# w65c265sxb_ym2149_rev1.net
KiCad netlist of a schematic drawn in EAGLE
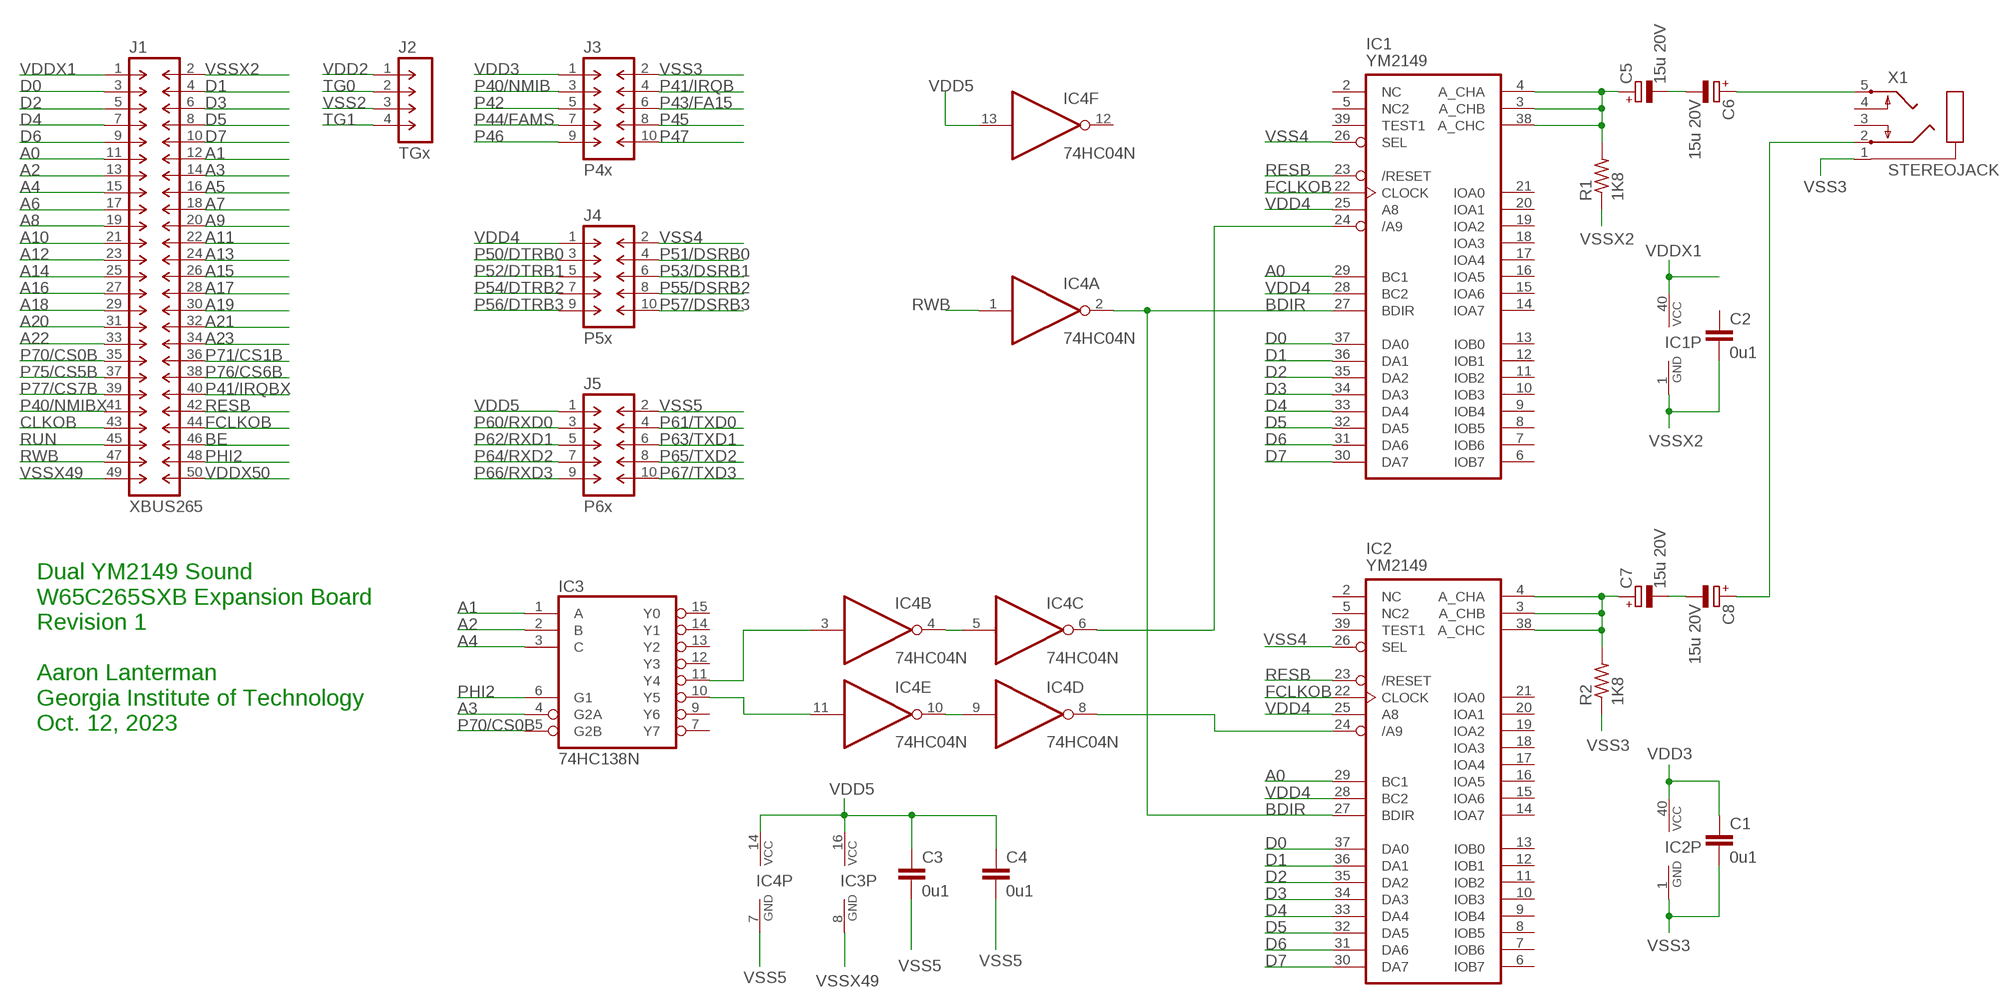
[diagram p0: schematic, sheet 1]

(export (version "E")
  (design (tool "Eeschema 10.0.6"))
  (components
    (comp (ref "C1")
      (value "0u1")
      (footprint "eagle-import:C050-025X075-AARON")
      (libsource (lib "eagle-import") (part "C-EU050-025X075-AARON"))
    )
    (comp (ref "C2")
      (value "0u1")
      (footprint "eagle-import:C050-025X075-AARON")
      (libsource (lib "eagle-import") (part "C-EU050-025X075-AARON"))
    )
    (comp (ref "C3")
      (value "0u1")
      (footprint "eagle-import:C050-025X075-AARON")
      (libsource (lib "eagle-import") (part "C-EU050-025X075-AARON"))
    )
    (comp (ref "C4")
      (value "0u1")
      (footprint "eagle-import:C050-025X075-AARON")
      (libsource (lib "eagle-import") (part "C-EU050-025X075-AARON"))
    )
    (comp (ref "C5")
      (value "15u 20V")
      (footprint "eagle-import:E2,5-7")
      (libsource (lib "eagle-import") (part "CPOL-EUE2.5-7"))
    )
    (comp (ref "C6")
      (value "15u 20V")
      (footprint "eagle-import:E2,5-7")
      (libsource (lib "eagle-import") (part "CPOL-EUE2.5-7"))
    )
    (comp (ref "C7")
      (value "15u 20V")
      (footprint "eagle-import:E2,5-7")
      (libsource (lib "eagle-import") (part "CPOL-EUE2.5-7"))
    )
    (comp (ref "C8")
      (value "15u 20V")
      (footprint "eagle-import:E2,5-7")
      (libsource (lib "eagle-import") (part "CPOL-EUE2.5-7"))
    )
    (comp (ref "IC1")
      (value "YM2149")
      (footprint "eagle-import:DIL40")
      (libsource (lib "eagle-import") (part "YM2149"))
    )
    (comp (ref "IC2")
      (value "YM2149")
      (footprint "eagle-import:DIL40")
      (libsource (lib "eagle-import") (part "YM2149"))
    )
    (comp (ref "IC3")
      (value "74HC138N")
      (footprint "eagle-import:DIL16")
      (libsource (lib "eagle-import") (part "74138NHC"))
    )
    (comp (ref "IC4")
      (value "74HC04N")
      (footprint "eagle-import:DIL14")
      (libsource (lib "eagle-import") (part "7404NHC"))
    )
    (comp (ref "J1")
      (value "XBUS265")
      (footprint "eagle-import:DIL-100-2X25")
      (libsource (lib "eagle-import") (part "M-2X25-DIL-100"))
    )
    (comp (ref "J2")
      (value "TGx")
      (footprint "eagle-import:SIP-100-04-40")
      (libsource (lib "eagle-import") (part "M-1X04-SIP-100-40"))
    )
    (comp (ref "J3")
      (value "P4x")
      (footprint "eagle-import:DIL-100-2X05")
      (libsource (lib "eagle-import") (part "M-2X05-DIL-100"))
    )
    (comp (ref "J4")
      (value "P5x")
      (footprint "eagle-import:DIL-100-2X05")
      (libsource (lib "eagle-import") (part "M-2X05-DIL-100"))
    )
    (comp (ref "J5")
      (value "P6x")
      (footprint "eagle-import:DIL-100-2X05")
      (libsource (lib "eagle-import") (part "M-2X05-DIL-100"))
    )
    (comp (ref "R1")
      (value "1K8")
      (footprint "eagle-import:0207_10")
      (libsource (lib "eagle-import") (part "R-US_0207/10"))
    )
    (comp (ref "R2")
      (value "1K8")
      (footprint "eagle-import:0207_10")
      (libsource (lib "eagle-import") (part "R-US_0207/10"))
    )
    (comp (ref "X1")
      (value "STEREOJACK")
      (footprint "eagle-import:STX3100")
      (libsource (lib "eagle-import") (part "STEREOJACK"))
    )
  )
  (nets
    (net (code "1") (name "/A0") (class "Default")
      (node (ref "IC1") (pin "29") (pinfunction "BC1_29") (pintype "input"))
      (node (ref "IC2") (pin "29") (pinfunction "BC1_29") (pintype "input"))
      (node (ref "J1") (pin "11") (pinfunction "11_11") (pintype "passive"))
    )
    (net (code "2") (name "/A1") (class "Default")
      (node (ref "IC3") (pin "1") (pinfunction "A_1") (pintype "input"))
      (node (ref "J1") (pin "12") (pinfunction "12_12") (pintype "passive"))
    )
    (net (code "3") (name "/A2") (class "Default")
      (node (ref "IC3") (pin "2") (pinfunction "B_2") (pintype "input"))
      (node (ref "J1") (pin "13") (pinfunction "13_13") (pintype "passive"))
    )
    (net (code "4") (name "/A3") (class "Default")
      (node (ref "IC3") (pin "4") (pinfunction "G2A_4") (pintype "input"))
      (node (ref "J1") (pin "14") (pinfunction "14_14") (pintype "passive"))
    )
    (net (code "5") (name "/A4") (class "Default")
      (node (ref "IC3") (pin "3") (pinfunction "C_3") (pintype "input"))
      (node (ref "J1") (pin "15") (pinfunction "15_15") (pintype "passive"))
    )
    (net (code "6") (name "/A5") (class "Default")
      (node (ref "J1") (pin "16") (pinfunction "16_16") (pintype "passive"))
    )
    (net (code "7") (name "/A6") (class "Default")
      (node (ref "J1") (pin "17") (pinfunction "17_17") (pintype "passive"))
    )
    (net (code "8") (name "/A7") (class "Default")
      (node (ref "J1") (pin "18") (pinfunction "18_18") (pintype "passive"))
    )
    (net (code "9") (name "/A8") (class "Default")
      (node (ref "J1") (pin "19") (pinfunction "19_19") (pintype "passive"))
    )
    (net (code "10") (name "/A9") (class "Default")
      (node (ref "J1") (pin "20") (pinfunction "20_20") (pintype "passive"))
    )
    (net (code "11") (name "/A10") (class "Default")
      (node (ref "J1") (pin "21") (pinfunction "21_21") (pintype "passive"))
    )
    (net (code "12") (name "/A11") (class "Default")
      (node (ref "J1") (pin "22") (pinfunction "22_22") (pintype "passive"))
    )
    (net (code "13") (name "/A12") (class "Default")
      (node (ref "J1") (pin "23") (pinfunction "23_23") (pintype "passive"))
    )
    (net (code "14") (name "/A13") (class "Default")
      (node (ref "J1") (pin "24") (pinfunction "24_24") (pintype "passive"))
    )
    (net (code "15") (name "/A14") (class "Default")
      (node (ref "J1") (pin "25") (pinfunction "25_25") (pintype "passive"))
    )
    (net (code "16") (name "/A15") (class "Default")
      (node (ref "J1") (pin "26") (pinfunction "26_26") (pintype "passive"))
    )
    (net (code "17") (name "/A16") (class "Default")
      (node (ref "J1") (pin "27") (pinfunction "27_27") (pintype "passive"))
    )
    (net (code "18") (name "/A17") (class "Default")
      (node (ref "J1") (pin "28") (pinfunction "28_28") (pintype "passive"))
    )
    (net (code "19") (name "/A18") (class "Default")
      (node (ref "J1") (pin "29") (pinfunction "29_29") (pintype "passive"))
    )
    (net (code "20") (name "/A19") (class "Default")
      (node (ref "J1") (pin "30") (pinfunction "30_30") (pintype "passive"))
    )
    (net (code "21") (name "/A20") (class "Default")
      (node (ref "J1") (pin "31") (pinfunction "31_31") (pintype "passive"))
    )
    (net (code "22") (name "/A21") (class "Default")
      (node (ref "J1") (pin "32") (pinfunction "32_32") (pintype "passive"))
    )
    (net (code "23") (name "/A22") (class "Default")
      (node (ref "J1") (pin "33") (pinfunction "33_33") (pintype "passive"))
    )
    (net (code "24") (name "/A23") (class "Default")
      (node (ref "J1") (pin "34") (pinfunction "34_34") (pintype "passive"))
    )
    (net (code "25") (name "/BDIR") (class "Default")
      (node (ref "IC1") (pin "27") (pinfunction "BDIR_27") (pintype "input"))
      (node (ref "IC2") (pin "27") (pinfunction "BDIR_27") (pintype "input"))
      (node (ref "IC4") (pin "2") (pinfunction "O_2") (pintype "output"))
    )
    (net (code "26") (name "/BE") (class "Default")
      (node (ref "J1") (pin "46") (pinfunction "46_46") (pintype "passive"))
    )
    (net (code "27") (name "/CLKOB") (class "Default")
      (node (ref "J1") (pin "43") (pinfunction "43_43") (pintype "passive"))
    )
    (net (code "28") (name "/D0") (class "Default")
      (node (ref "IC1") (pin "37") (pinfunction "DA0_37") (pintype "bidirectional"))
      (node (ref "IC2") (pin "37") (pinfunction "DA0_37") (pintype "bidirectional"))
      (node (ref "J1") (pin "3") (pinfunction "3_3") (pintype "passive"))
    )
    (net (code "29") (name "/D1") (class "Default")
      (node (ref "IC1") (pin "36") (pinfunction "DA1_36") (pintype "bidirectional"))
      (node (ref "IC2") (pin "36") (pinfunction "DA1_36") (pintype "bidirectional"))
      (node (ref "J1") (pin "4") (pinfunction "4_4") (pintype "passive"))
    )
    (net (code "30") (name "/D2") (class "Default")
      (node (ref "IC1") (pin "35") (pinfunction "DA2_35") (pintype "bidirectional"))
      (node (ref "IC2") (pin "35") (pinfunction "DA2_35") (pintype "bidirectional"))
      (node (ref "J1") (pin "5") (pinfunction "5_5") (pintype "passive"))
    )
    (net (code "31") (name "/D3") (class "Default")
      (node (ref "IC1") (pin "34") (pinfunction "DA3_34") (pintype "bidirectional"))
      (node (ref "IC2") (pin "34") (pinfunction "DA3_34") (pintype "bidirectional"))
      (node (ref "J1") (pin "6") (pinfunction "6_6") (pintype "passive"))
    )
    (net (code "32") (name "/D4") (class "Default")
      (node (ref "IC1") (pin "33") (pinfunction "DA4_33") (pintype "bidirectional"))
      (node (ref "IC2") (pin "33") (pinfunction "DA4_33") (pintype "bidirectional"))
      (node (ref "J1") (pin "7") (pinfunction "7_7") (pintype "passive"))
    )
    (net (code "33") (name "/D5") (class "Default")
      (node (ref "IC1") (pin "32") (pinfunction "DA5_32") (pintype "bidirectional"))
      (node (ref "IC2") (pin "32") (pinfunction "DA5_32") (pintype "bidirectional"))
      (node (ref "J1") (pin "8") (pinfunction "8_8") (pintype "passive"))
    )
    (net (code "34") (name "/D6") (class "Default")
      (node (ref "IC1") (pin "31") (pinfunction "DA6_31") (pintype "bidirectional"))
      (node (ref "IC2") (pin "31") (pinfunction "DA6_31") (pintype "bidirectional"))
      (node (ref "J1") (pin "9") (pinfunction "9_9") (pintype "passive"))
    )
    (net (code "35") (name "/D7") (class "Default")
      (node (ref "IC1") (pin "30") (pinfunction "DA7_30") (pintype "bidirectional"))
      (node (ref "IC2") (pin "30") (pinfunction "DA7_30") (pintype "bidirectional"))
      (node (ref "J1") (pin "10") (pinfunction "10_10") (pintype "passive"))
    )
    (net (code "36") (name "/FCLKOB") (class "Default")
      (node (ref "IC1") (pin "22") (pinfunction "CLOCK_22") (pintype "input"))
      (node (ref "IC2") (pin "22") (pinfunction "CLOCK_22") (pintype "input"))
      (node (ref "J1") (pin "44") (pinfunction "44_44") (pintype "passive"))
    )
    (net (code "37") (name "/P40{slash}NMIB") (class "Default")
      (node (ref "J3") (pin "3") (pinfunction "3_3") (pintype "passive"))
    )
    (net (code "38") (name "/P40{slash}NMIBX") (class "Default")
      (node (ref "J1") (pin "41") (pinfunction "41_41") (pintype "passive"))
    )
    (net (code "39") (name "/P41{slash}IRQB") (class "Default")
      (node (ref "J3") (pin "4") (pinfunction "4_4") (pintype "passive"))
    )
    (net (code "40") (name "/P41{slash}IRQBX") (class "Default")
      (node (ref "J1") (pin "40") (pinfunction "40_40") (pintype "passive"))
    )
    (net (code "41") (name "/P42") (class "Default")
      (node (ref "J3") (pin "5") (pinfunction "5_5") (pintype "passive"))
    )
    (net (code "42") (name "/P43{slash}FA15") (class "Default")
      (node (ref "J3") (pin "6") (pinfunction "6_6") (pintype "passive"))
    )
    (net (code "43") (name "/P44{slash}FAMS") (class "Default")
      (node (ref "J3") (pin "7") (pinfunction "7_7") (pintype "passive"))
    )
    (net (code "44") (name "/P45") (class "Default")
      (node (ref "J3") (pin "8") (pinfunction "8_8") (pintype "passive"))
    )
    (net (code "45") (name "/P46") (class "Default")
      (node (ref "J3") (pin "9") (pinfunction "9_9") (pintype "passive"))
    )
    (net (code "46") (name "/P47") (class "Default")
      (node (ref "J3") (pin "10") (pinfunction "10_10") (pintype "passive"))
    )
    (net (code "47") (name "/P50{slash}DTRB0") (class "Default")
      (node (ref "J4") (pin "3") (pinfunction "3_3") (pintype "passive"))
    )
    (net (code "48") (name "/P51{slash}DSRB0") (class "Default")
      (node (ref "J4") (pin "4") (pinfunction "4_4") (pintype "passive"))
    )
    (net (code "49") (name "/P52{slash}DTRB1") (class "Default")
      (node (ref "J4") (pin "5") (pinfunction "5_5") (pintype "passive"))
    )
    (net (code "50") (name "/P53{slash}DSRB1") (class "Default")
      (node (ref "J4") (pin "6") (pinfunction "6_6") (pintype "passive"))
    )
    (net (code "51") (name "/P54{slash}DTRB2") (class "Default")
      (node (ref "J4") (pin "7") (pinfunction "7_7") (pintype "passive"))
    )
    (net (code "52") (name "/P55{slash}DSRB2") (class "Default")
      (node (ref "J4") (pin "8") (pinfunction "8_8") (pintype "passive"))
    )
    (net (code "53") (name "/P56{slash}DTRB3") (class "Default")
      (node (ref "J4") (pin "9") (pinfunction "9_9") (pintype "passive"))
    )
    (net (code "54") (name "/P57{slash}DSRB3") (class "Default")
      (node (ref "J4") (pin "10") (pinfunction "10_10") (pintype "passive"))
    )
    (net (code "55") (name "/P60{slash}RXD0") (class "Default")
      (node (ref "J5") (pin "3") (pinfunction "3_3") (pintype "passive"))
    )
    (net (code "56") (name "/P61{slash}TXD0") (class "Default")
      (node (ref "J5") (pin "4") (pinfunction "4_4") (pintype "passive"))
    )
    (net (code "57") (name "/P62{slash}RXD1") (class "Default")
      (node (ref "J5") (pin "5") (pinfunction "5_5") (pintype "passive"))
    )
    (net (code "58") (name "/P63{slash}TXD1") (class "Default")
      (node (ref "J5") (pin "6") (pinfunction "6_6") (pintype "passive"))
    )
    (net (code "59") (name "/P64{slash}RXD2") (class "Default")
      (node (ref "J5") (pin "7") (pinfunction "7_7") (pintype "passive"))
    )
    (net (code "60") (name "/P65{slash}TXD2") (class "Default")
      (node (ref "J5") (pin "8") (pinfunction "8_8") (pintype "passive"))
    )
    (net (code "61") (name "/P66{slash}RXD3") (class "Default")
      (node (ref "J5") (pin "9") (pinfunction "9_9") (pintype "passive"))
    )
    (net (code "62") (name "/P67{slash}TXD3") (class "Default")
      (node (ref "J5") (pin "10") (pinfunction "10_10") (pintype "passive"))
    )
    (net (code "63") (name "/P70{slash}CS0B") (class "Default")
      (node (ref "IC3") (pin "5") (pinfunction "G2B_5") (pintype "input"))
      (node (ref "J1") (pin "35") (pinfunction "35_35") (pintype "passive"))
    )
    (net (code "64") (name "/P71{slash}CS1B") (class "Default")
      (node (ref "J1") (pin "36") (pinfunction "36_36") (pintype "passive"))
    )
    (net (code "65") (name "/P75{slash}CS5B") (class "Default")
      (node (ref "J1") (pin "37") (pinfunction "37_37") (pintype "passive"))
    )
    (net (code "66") (name "/P76{slash}CS6B") (class "Default")
      (node (ref "J1") (pin "38") (pinfunction "38_38") (pintype "passive"))
    )
    (net (code "67") (name "/P77{slash}CS7B") (class "Default")
      (node (ref "J1") (pin "39") (pinfunction "39_39") (pintype "passive"))
    )
    (net (code "68") (name "/PHI2") (class "Default")
      (node (ref "IC3") (pin "6") (pinfunction "G1_6") (pintype "input"))
      (node (ref "J1") (pin "48") (pinfunction "48_48") (pintype "passive"))
    )
    (net (code "69") (name "/RESB") (class "Default")
      (node (ref "IC1") (pin "23") (pinfunction "/RESET_23") (pintype "input"))
      (node (ref "IC2") (pin "23") (pinfunction "/RESET_23") (pintype "input"))
      (node (ref "J1") (pin "42") (pinfunction "42_42") (pintype "passive"))
    )
    (net (code "70") (name "/RUN") (class "Default")
      (node (ref "J1") (pin "45") (pinfunction "45_45") (pintype "passive"))
    )
    (net (code "71") (name "/RWB") (class "Default")
      (node (ref "IC4") (pin "1") (pinfunction "I_1") (pintype "input"))
      (node (ref "J1") (pin "47") (pinfunction "47_47") (pintype "passive"))
    )
    (net (code "72") (name "/TG0") (class "Default")
      (node (ref "J2") (pin "2") (pinfunction "2_2") (pintype "passive"))
    )
    (net (code "73") (name "/TG1") (class "Default")
      (node (ref "J2") (pin "4") (pinfunction "4_4") (pintype "passive"))
    )
    (net (code "74") (name "/VDD2") (class "Default")
      (node (ref "J2") (pin "1") (pinfunction "1_1") (pintype "passive"))
    )
    (net (code "75") (name "/VDD3") (class "Default")
      (node (ref "C1") (pin "1") (pinfunction "1_1") (pintype "passive"))
      (node (ref "IC2") (pin "40") (pinfunction "VCC_40") (pintype "power_in"))
      (node (ref "J3") (pin "1") (pinfunction "1_1") (pintype "passive"))
    )
    (net (code "76") (name "/VDD4") (class "Default")
      (node (ref "IC1") (pin "25") (pinfunction "A8_25") (pintype "input"))
      (node (ref "IC1") (pin "28") (pinfunction "BC2_28") (pintype "input"))
      (node (ref "IC2") (pin "25") (pinfunction "A8_25") (pintype "input"))
      (node (ref "IC2") (pin "28") (pinfunction "BC2_28") (pintype "input"))
      (node (ref "J4") (pin "1") (pinfunction "1_1") (pintype "passive"))
    )
    (net (code "77") (name "/VDD5") (class "Default")
      (node (ref "C3") (pin "1") (pinfunction "1_1") (pintype "passive"))
      (node (ref "C4") (pin "1") (pinfunction "1_1") (pintype "passive"))
      (node (ref "IC3") (pin "16") (pinfunction "VCC_16") (pintype "power_in"))
      (node (ref "IC4") (pin "13") (pinfunction "I_13") (pintype "input"))
      (node (ref "IC4") (pin "14") (pinfunction "VCC_14") (pintype "power_in"))
      (node (ref "J5") (pin "1") (pinfunction "1_1") (pintype "passive"))
    )
    (net (code "78") (name "/VDDX1") (class "Default")
      (node (ref "IC1") (pin "40") (pinfunction "VCC_40") (pintype "power_in"))
      (node (ref "J1") (pin "1") (pinfunction "1_1") (pintype "passive"))
    )
    (net (code "79") (name "/VDDX50") (class "Default")
      (node (ref "J1") (pin "50") (pinfunction "50_50") (pintype "passive"))
    )
    (net (code "80") (name "/VSS2") (class "Default")
      (node (ref "J2") (pin "3") (pinfunction "3_3") (pintype "passive"))
    )
    (net (code "81") (name "/VSS3") (class "Default")
      (node (ref "C1") (pin "2") (pinfunction "2_2") (pintype "passive"))
      (node (ref "IC2") (pin "1") (pinfunction "GND_1") (pintype "power_in"))
      (node (ref "J3") (pin "2") (pinfunction "2_2") (pintype "passive"))
      (node (ref "R2") (pin "1") (pinfunction "1_1") (pintype "passive"))
      (node (ref "X1") (pin "1") (pinfunction "1_1") (pintype "passive"))
    )
    (net (code "82") (name "/VSS4") (class "Default")
      (node (ref "IC1") (pin "26") (pinfunction "SEL_26") (pintype "input"))
      (node (ref "IC2") (pin "26") (pinfunction "SEL_26") (pintype "input"))
      (node (ref "J4") (pin "2") (pinfunction "2_2") (pintype "passive"))
    )
    (net (code "83") (name "/VSS5") (class "Default")
      (node (ref "C3") (pin "2") (pinfunction "2_2") (pintype "passive"))
      (node (ref "C4") (pin "2") (pinfunction "2_2") (pintype "passive"))
      (node (ref "IC4") (pin "7") (pinfunction "GND_7") (pintype "power_in"))
      (node (ref "J5") (pin "2") (pinfunction "2_2") (pintype "passive"))
    )
    (net (code "84") (name "/VSSX2") (class "Default")
      (node (ref "C2") (pin "2") (pinfunction "2_2") (pintype "passive"))
      (node (ref "IC1") (pin "1") (pinfunction "GND_1") (pintype "power_in"))
      (node (ref "J1") (pin "2") (pinfunction "2_2") (pintype "passive"))
      (node (ref "R1") (pin "1") (pinfunction "1_1") (pintype "passive"))
    )
    (net (code "85") (name "/VSSX49") (class "Default")
      (node (ref "IC3") (pin "8") (pinfunction "GND_8") (pintype "power_in"))
      (node (ref "J1") (pin "49") (pinfunction "49_49") (pintype "passive"))
    )
    (net (code "86") (name "Net-(C5-Pad-)") (class "Default")
      (node (ref "C5") (pin "-") (pinfunction "-_-") (pintype "passive"))
      (node (ref "C6") (pin "-") (pinfunction "-_-") (pintype "passive"))
    )
    (net (code "87") (name "Net-(C6-Pad+)") (class "Default")
      (node (ref "C6") (pin "+") (pinfunction "+_+") (pintype "passive"))
      (node (ref "X1") (pin "5") (pinfunction "5_5") (pintype "passive"))
    )
    (net (code "88") (name "Net-(C7-Pad-)") (class "Default")
      (node (ref "C7") (pin "-") (pinfunction "-_-") (pintype "passive"))
      (node (ref "C8") (pin "-") (pinfunction "-_-") (pintype "passive"))
    )
    (net (code "89") (name "Net-(C8-Pad+)") (class "Default")
      (node (ref "C8") (pin "+") (pinfunction "+_+") (pintype "passive"))
      (node (ref "X1") (pin "2") (pinfunction "2_2") (pintype "passive"))
    )
    (net (code "90") (name "Net-(IC1A-A_CHA)") (class "Default")
      (node (ref "C5") (pin "+") (pinfunction "+_+") (pintype "passive"))
      (node (ref "IC1") (pin "3") (pinfunction "A_CHB_3") (pintype "output"))
      (node (ref "IC1") (pin "38") (pinfunction "A_CHC_38") (pintype "output"))
      (node (ref "IC1") (pin "4") (pinfunction "A_CHA_4") (pintype "output"))
      (node (ref "R1") (pin "2") (pinfunction "2_2") (pintype "passive"))
    )
    (net (code "91") (name "Net-(IC1A-{slash}A9)") (class "Default")
      (node (ref "IC1") (pin "24") (pinfunction "/A9_24") (pintype "input"))
      (node (ref "IC4") (pin "6") (pinfunction "O_6") (pintype "output"))
    )
    (net (code "92") (name "Net-(IC2A-A_CHA)") (class "Default")
      (node (ref "C7") (pin "+") (pinfunction "+_+") (pintype "passive"))
      (node (ref "IC2") (pin "3") (pinfunction "A_CHB_3") (pintype "output"))
      (node (ref "IC2") (pin "38") (pinfunction "A_CHC_38") (pintype "output"))
      (node (ref "IC2") (pin "4") (pinfunction "A_CHA_4") (pintype "output"))
      (node (ref "R2") (pin "2") (pinfunction "2_2") (pintype "passive"))
    )
    (net (code "93") (name "Net-(IC2A-{slash}A9)") (class "Default")
      (node (ref "IC2") (pin "24") (pinfunction "/A9_24") (pintype "input"))
      (node (ref "IC4") (pin "8") (pinfunction "O_8") (pintype "output"))
    )
    (net (code "94") (name "Net-(IC3A-Y4)") (class "Default")
      (node (ref "IC3") (pin "11") (pinfunction "Y4_11") (pintype "output"))
      (node (ref "IC4") (pin "3") (pinfunction "I_3") (pintype "input"))
    )
    (net (code "95") (name "Net-(IC3A-Y5)") (class "Default")
      (node (ref "IC3") (pin "10") (pinfunction "Y5_10") (pintype "output"))
      (node (ref "IC4") (pin "11") (pinfunction "I_11") (pintype "input"))
    )
    (net (code "96") (name "Net-(IC4B-O)") (class "Default")
      (node (ref "IC4") (pin "4") (pinfunction "O_4") (pintype "output"))
      (node (ref "IC4") (pin "5") (pinfunction "I_5") (pintype "input"))
    )
    (net (code "97") (name "Net-(IC4D-I)") (class "Default")
      (node (ref "IC4") (pin "10") (pinfunction "O_10") (pintype "output"))
      (node (ref "IC4") (pin "9") (pinfunction "I_9") (pintype "input"))
    )
    (net (code "98") (name "unconnected-(C2-Pad1)") (class "Default")
      (node (ref "C2") (pin "1") (pinfunction "1_1") (pintype "passive"))
    )
    (net (code "99") (name "unconnected-(IC1A-IOA0-Pad21)") (class "Default")
      (node (ref "IC1") (pin "21") (pinfunction "IOA0_21") (pintype "bidirectional"))
    )
    (net (code "100") (name "unconnected-(IC1A-IOA1-Pad20)") (class "Default")
      (node (ref "IC1") (pin "20") (pinfunction "IOA1_20") (pintype "bidirectional"))
    )
    (net (code "101") (name "unconnected-(IC1A-IOA2-Pad19)") (class "Default")
      (node (ref "IC1") (pin "19") (pinfunction "IOA2_19") (pintype "bidirectional"))
    )
    (net (code "102") (name "unconnected-(IC1A-IOA3-Pad18)") (class "Default")
      (node (ref "IC1") (pin "18") (pinfunction "IOA3_18") (pintype "bidirectional"))
    )
    (net (code "103") (name "unconnected-(IC1A-IOA4-Pad17)") (class "Default")
      (node (ref "IC1") (pin "17") (pinfunction "IOA4_17") (pintype "bidirectional"))
    )
    (net (code "104") (name "unconnected-(IC1A-IOA5-Pad16)") (class "Default")
      (node (ref "IC1") (pin "16") (pinfunction "IOA5_16") (pintype "bidirectional"))
    )
    (net (code "105") (name "unconnected-(IC1A-IOA6-Pad15)") (class "Default")
      (node (ref "IC1") (pin "15") (pinfunction "IOA6_15") (pintype "bidirectional"))
    )
    (net (code "106") (name "unconnected-(IC1A-IOA7-Pad14)") (class "Default")
      (node (ref "IC1") (pin "14") (pinfunction "IOA7_14") (pintype "bidirectional"))
    )
    (net (code "107") (name "unconnected-(IC1A-IOB0-Pad13)") (class "Default")
      (node (ref "IC1") (pin "13") (pinfunction "IOB0_13") (pintype "bidirectional"))
    )
    (net (code "108") (name "unconnected-(IC1A-IOB1-Pad12)") (class "Default")
      (node (ref "IC1") (pin "12") (pinfunction "IOB1_12") (pintype "bidirectional"))
    )
    (net (code "109") (name "unconnected-(IC1A-IOB2-Pad11)") (class "Default")
      (node (ref "IC1") (pin "11") (pinfunction "IOB2_11") (pintype "bidirectional"))
    )
    (net (code "110") (name "unconnected-(IC1A-IOB3-Pad10)") (class "Default")
      (node (ref "IC1") (pin "10") (pinfunction "IOB3_10") (pintype "bidirectional"))
    )
    (net (code "111") (name "unconnected-(IC1A-IOB4-Pad9)") (class "Default")
      (node (ref "IC1") (pin "9") (pinfunction "IOB4_9") (pintype "bidirectional"))
    )
    (net (code "112") (name "unconnected-(IC1A-IOB5-Pad8)") (class "Default")
      (node (ref "IC1") (pin "8") (pinfunction "IOB5_8") (pintype "bidirectional"))
    )
    (net (code "113") (name "unconnected-(IC1A-IOB6-Pad7)") (class "Default")
      (node (ref "IC1") (pin "7") (pinfunction "IOB6_7") (pintype "bidirectional"))
    )
    (net (code "114") (name "unconnected-(IC1A-IOB7-Pad6)") (class "Default")
      (node (ref "IC1") (pin "6") (pinfunction "IOB7_6") (pintype "bidirectional"))
    )
    (net (code "115") (name "unconnected-(IC1A-NC-Pad2)") (class "Default")
      (node (ref "IC1") (pin "2") (pinfunction "NC_2") (pintype "no_connect"))
    )
    (net (code "116") (name "unconnected-(IC1A-NC2-Pad5)") (class "Default")
      (node (ref "IC1") (pin "5") (pinfunction "NC2_5") (pintype "no_connect"))
    )
    (net (code "117") (name "unconnected-(IC1A-TEST1-Pad39)") (class "Default")
      (node (ref "IC1") (pin "39") (pinfunction "TEST1_39") (pintype "input"))
    )
    (net (code "118") (name "unconnected-(IC2A-IOA0-Pad21)") (class "Default")
      (node (ref "IC2") (pin "21") (pinfunction "IOA0_21") (pintype "bidirectional"))
    )
    (net (code "119") (name "unconnected-(IC2A-IOA1-Pad20)") (class "Default")
      (node (ref "IC2") (pin "20") (pinfunction "IOA1_20") (pintype "bidirectional"))
    )
    (net (code "120") (name "unconnected-(IC2A-IOA2-Pad19)") (class "Default")
      (node (ref "IC2") (pin "19") (pinfunction "IOA2_19") (pintype "bidirectional"))
    )
    (net (code "121") (name "unconnected-(IC2A-IOA3-Pad18)") (class "Default")
      (node (ref "IC2") (pin "18") (pinfunction "IOA3_18") (pintype "bidirectional"))
    )
    (net (code "122") (name "unconnected-(IC2A-IOA4-Pad17)") (class "Default")
      (node (ref "IC2") (pin "17") (pinfunction "IOA4_17") (pintype "bidirectional"))
    )
    (net (code "123") (name "unconnected-(IC2A-IOA5-Pad16)") (class "Default")
      (node (ref "IC2") (pin "16") (pinfunction "IOA5_16") (pintype "bidirectional"))
    )
    (net (code "124") (name "unconnected-(IC2A-IOA6-Pad15)") (class "Default")
      (node (ref "IC2") (pin "15") (pinfunction "IOA6_15") (pintype "bidirectional"))
    )
    (net (code "125") (name "unconnected-(IC2A-IOA7-Pad14)") (class "Default")
      (node (ref "IC2") (pin "14") (pinfunction "IOA7_14") (pintype "bidirectional"))
    )
    (net (code "126") (name "unconnected-(IC2A-IOB0-Pad13)") (class "Default")
      (node (ref "IC2") (pin "13") (pinfunction "IOB0_13") (pintype "bidirectional"))
    )
    (net (code "127") (name "unconnected-(IC2A-IOB1-Pad12)") (class "Default")
      (node (ref "IC2") (pin "12") (pinfunction "IOB1_12") (pintype "bidirectional"))
    )
    (net (code "128") (name "unconnected-(IC2A-IOB2-Pad11)") (class "Default")
      (node (ref "IC2") (pin "11") (pinfunction "IOB2_11") (pintype "bidirectional"))
    )
    (net (code "129") (name "unconnected-(IC2A-IOB3-Pad10)") (class "Default")
      (node (ref "IC2") (pin "10") (pinfunction "IOB3_10") (pintype "bidirectional"))
    )
    (net (code "130") (name "unconnected-(IC2A-IOB4-Pad9)") (class "Default")
      (node (ref "IC2") (pin "9") (pinfunction "IOB4_9") (pintype "bidirectional"))
    )
    (net (code "131") (name "unconnected-(IC2A-IOB5-Pad8)") (class "Default")
      (node (ref "IC2") (pin "8") (pinfunction "IOB5_8") (pintype "bidirectional"))
    )
    (net (code "132") (name "unconnected-(IC2A-IOB6-Pad7)") (class "Default")
      (node (ref "IC2") (pin "7") (pinfunction "IOB6_7") (pintype "bidirectional"))
    )
    (net (code "133") (name "unconnected-(IC2A-IOB7-Pad6)") (class "Default")
      (node (ref "IC2") (pin "6") (pinfunction "IOB7_6") (pintype "bidirectional"))
    )
    (net (code "134") (name "unconnected-(IC2A-NC-Pad2)") (class "Default")
      (node (ref "IC2") (pin "2") (pinfunction "NC_2") (pintype "no_connect"))
    )
    (net (code "135") (name "unconnected-(IC2A-NC2-Pad5)") (class "Default")
      (node (ref "IC2") (pin "5") (pinfunction "NC2_5") (pintype "no_connect"))
    )
    (net (code "136") (name "unconnected-(IC2A-TEST1-Pad39)") (class "Default")
      (node (ref "IC2") (pin "39") (pinfunction "TEST1_39") (pintype "input"))
    )
    (net (code "137") (name "unconnected-(IC3A-Y0-Pad15)") (class "Default")
      (node (ref "IC3") (pin "15") (pinfunction "Y0_15") (pintype "output"))
    )
    (net (code "138") (name "unconnected-(IC3A-Y1-Pad14)") (class "Default")
      (node (ref "IC3") (pin "14") (pinfunction "Y1_14") (pintype "output"))
    )
    (net (code "139") (name "unconnected-(IC3A-Y2-Pad13)") (class "Default")
      (node (ref "IC3") (pin "13") (pinfunction "Y2_13") (pintype "output"))
    )
    (net (code "140") (name "unconnected-(IC3A-Y3-Pad12)") (class "Default")
      (node (ref "IC3") (pin "12") (pinfunction "Y3_12") (pintype "output"))
    )
    (net (code "141") (name "unconnected-(IC3A-Y6-Pad9)") (class "Default")
      (node (ref "IC3") (pin "9") (pinfunction "Y6_9") (pintype "output"))
    )
    (net (code "142") (name "unconnected-(IC3A-Y7-Pad7)") (class "Default")
      (node (ref "IC3") (pin "7") (pinfunction "Y7_7") (pintype "output"))
    )
    (net (code "143") (name "unconnected-(IC4F-O-Pad12)") (class "Default")
      (node (ref "IC4") (pin "12") (pinfunction "O_12") (pintype "output"))
    )
    (net (code "144") (name "unconnected-(X1-Pad3)") (class "Default")
      (node (ref "X1") (pin "3") (pinfunction "3_3") (pintype "passive"))
    )
    (net (code "145") (name "unconnected-(X1-Pad4)") (class "Default")
      (node (ref "X1") (pin "4") (pinfunction "4_4") (pintype "passive"))
    )
  )
)
